# Eth-Crystal.net
KiCad netlist of a schematic drawn in Altium Designer
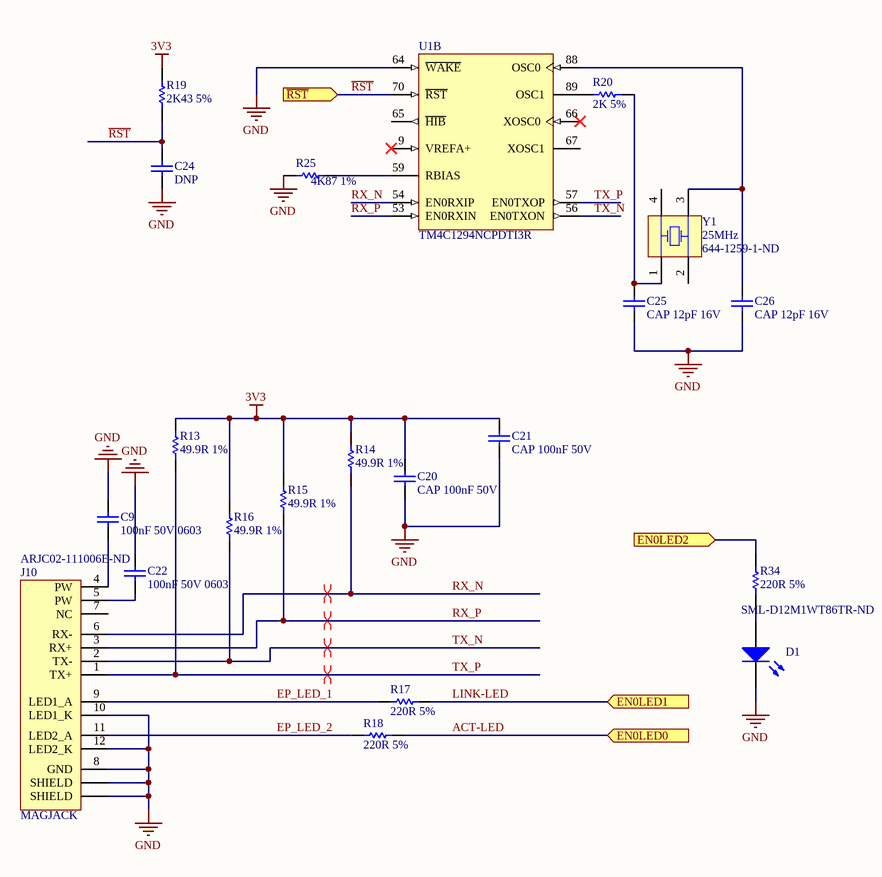
[diagram p0: Eth-Crystal.SchDoc]

(export (version "E")
  (design (tool "Eeschema 10.0.6"))
  (components
    (comp (ref "C9")
      (value "100nF 50V 0603")
      (footprint "CAPC0603(1608)100_M")
      (description "CAP 100nF 50V -20% to +80% 0603 (1608 Metric) Thickness 1mm SMD")
      (fields (field (name "TOLERANCE") "-20% to +80%"))
      (libsource (lib "Altium Content Vault") (part "CMP-1035-02594-1"))
    )
    (comp (ref "C20")
      (value "CAP 100nF 50V")
      (footprint "CAPC0603(1608)100_M")
      (description "CAP 100nF 50V Â±0.1pF 0603 (1608 Metric) Thickness 1mm SMD")
      (fields (field (name "TOLERANCE") "Â±0.1pF"))
      (libsource (lib "Altium Content Vault") (part "CMP-1035-00010-1"))
    )
    (comp (ref "C21")
      (value "CAP 100nF 50V")
      (footprint "CAPC0603(1608)100_M")
      (description "CAP 100nF 50V Â±0.1pF 0603 (1608 Metric) Thickness 1mm SMD")
      (fields (field (name "TOLERANCE") "Â±0.1pF"))
      (libsource (lib "Altium Content Vault") (part "CMP-1035-00010-1"))
    )
    (comp (ref "C22")
      (value "100nF 50V 0603")
      (footprint "CAPC0603(1608)100_M")
      (description "CAP 100nF 50V -20% to +80% 0603 (1608 Metric) Thickness 1mm SMD")
      (fields (field (name "TOLERANCE") "-20% to +80%"))
      (libsource (lib "Altium Content Vault") (part "CMP-1035-02594-1"))
    )
    (comp (ref "C24")
      (value "DNP")
      (footprint "0603")
      (description "100nF")
      (fields (field (name "PUBLISHER") "Altium Limited"))
      (libsource (lib "HSBNE-MAIN") (part "Cap_100pF"))
    )
    (comp (ref "C25")
      (value "CAP 12pF 16V")
      (footprint "CAPC0603(1608)100_L")
      (description "CAP 12pF 16V Â±0.25pF 0603 (1608 Metric) Thickness 1mm SMD")
      (fields (field (name "TOLERANCE") "Â±0.25pF"))
      (libsource (lib "Altium Content Vault") (part "CAP"))
    )
    (comp (ref "C26")
      (value "CAP 12pF 16V")
      (footprint "CAPC0603(1608)100_L")
      (description "CAP 12pF 16V Â±0.25pF 0603 (1608 Metric) Thickness 1mm SMD")
      (fields (field (name "TOLERANCE") "Â±0.25pF"))
      (libsource (lib "Altium Content Vault") (part "CAP"))
    )
    (comp (ref "D1")
      (value "LED")
      (footprint "LED-0603")
      (description "Typical RED, GREEN, YELLOW, AMBER GaAs LED")
      (fields
        (field (name "SUPPLIER PART NUMBER 2") "SML-D12M1WT86TR-ND")
        (field (name "PUBLISHER") "Altium Limited")
      )
      (libsource (lib "HSBNE-Vend") (part "LED"))
    )
    (comp (ref "J10")
      (value "MAGJACK")
      (footprint "magjack")
      (fields (field (name "SUPPLIER PART NUMBER 2") "ARJC02-111006E-ND"))
      (libsource (lib "HSBNE-MAIN") (part "MagJack"))
    )
    (comp (ref "R13")
      (value "49.9R 1%")
      (footprint "RESC0603(1608)_M")
      (description "49.9R 0.1W 1% 0603 (1608 Metric)  SMD")
      (fields (field (name "TOLERANCE") "5 %") (field (name "POWER") "0.1 W"))
      (libsource (lib "Altium Content Vault") (part "CMP-1012-00042-1"))
    )
    (comp (ref "R14")
      (value "49.9R 1%")
      (footprint "RESC0603(1608)_M")
      (description "49.9R 0.1W 1% 0603 (1608 Metric)  SMD")
      (fields (field (name "TOLERANCE") "5 %") (field (name "POWER") "0.1 W"))
      (libsource (lib "Altium Content Vault") (part "CMP-1012-00042-1"))
    )
    (comp (ref "R15")
      (value "49.9R 1%")
      (footprint "RESC0603(1608)_M")
      (description "49.9R 0.1W 1% 0603 (1608 Metric)  SMD")
      (fields (field (name "TOLERANCE") "5 %") (field (name "POWER") "0.1 W"))
      (libsource (lib "Altium Content Vault") (part "CMP-1012-00042-1"))
    )
    (comp (ref "R16")
      (value "49.9R 1%")
      (footprint "RESC0603(1608)_M")
      (description "49.9R 0.1W 1% 0603 (1608 Metric)  SMD")
      (fields (field (name "TOLERANCE") "5 %") (field (name "POWER") "0.1 W"))
      (libsource (lib "Altium Content Vault") (part "CMP-1012-00042-1"))
    )
    (comp (ref "R17")
      (value "220R 5%")
      (footprint "RESC0603(1608)_M")
      (description "220R 0.1W 5% 0603 (1608 Metric)  SMD")
      (fields (field (name "POWER") "0.1 W") (field (name "TOLERANCE") "5 %"))
      (libsource (lib "Altium Content Vault") (part "CMP-1012-00058-1"))
    )
    (comp (ref "R18")
      (value "220R 5%")
      (footprint "RESC0603(1608)_M")
      (description "220R 0.1W 5% 0603 (1608 Metric)  SMD")
      (fields (field (name "POWER") "0.1 W") (field (name "TOLERANCE") "5 %"))
      (libsource (lib "Altium Content Vault") (part "CMP-1012-00058-1"))
    )
    (comp (ref "R19")
      (value "2K43 5%")
      (footprint "RESC0603(1608)_M")
      (description "2K43 0.1W 5% 0603 (1608 Metric)  SMD")
      (fields (field (name "TOLERANCE") "5 %") (field (name "POWER") "0.1 W"))
      (libsource (lib "Altium Content Vault") (part "CMP-1012-00083-1"))
    )
    (comp (ref "R20")
      (value "2K 5%")
      (footprint "RESC0603(1608)_N")
      (description "2K 0.1W 5% 0603 (1608 Metric)  SMD")
      (fields (field (name "TOLERANCE") "5 %") (field (name "POWER") "0.1 W"))
      (libsource (lib "Altium Content Vault") (part "RES"))
    )
    (comp (ref "R25")
      (value "4K87 1%")
      (footprint "RESC0603(1608)_M")
      (description "4K87 0.1W 1% 0603 (1608 Metric)  SMD")
      (fields (field (name "TOLERANCE") "5 %") (field (name "POWER") "0.1 W"))
      (libsource (lib "Altium Content Vault") (part "CMP-1012-00090-1"))
    )
    (comp (ref "R34")
      (value "220R 5%")
      (footprint "RESC0603(1608)_M")
      (description "220R 0.1W 5% 0603 (1608 Metric)  SMD")
      (fields (field (name "POWER") "0.1 W") (field (name "TOLERANCE") "5 %"))
      (libsource (lib "Altium Content Vault") (part "CMP-1012-00058-1"))
    )
    (comp (ref "U1")
      (value "TM4C1294NCPDTI3R")
      (footprint "TI-PDT128_M")
      (fields (field (name "MANUFACTURER") "Texas Instruments"))
      (libsource (lib "Altium Inc") (part "TI-TM4C1294NCPDT-128"))
    )
    (comp (ref "Y1")
      (value "25MHz")
      (footprint "Crystal 3.2x2.5")
      (description "Surface Mount Quartz Crystal")
      (fields
        (field (name "SUPPLIER PART NUMBER 1") "644-1259-1-ND")
        (field (name "PUBLISHER") "Altium Limited")
      )
      (libsource (lib "HSBNE-Vend") (part "Crystal_25MHz"))
    )
  )
  (nets
    (net (code "1") (name "/ACT-LED") (class "Default")
      (node (ref "R18") (pin "2") (pinfunction "2_2") (pintype "passive"))
    )
    (net (code "2") (name "/EN0LED2") (class "Default")
      (node (ref "R34") (pin "2") (pinfunction "2_2") (pintype "passive"))
    )
    (net (code "3") (name "/EP_LED_1") (class "Default")
      (node (ref "J10") (pin "9") (pinfunction "LED1_A_9") (pintype "passive"))
      (node (ref "R17") (pin "1") (pinfunction "1_1") (pintype "passive"))
    )
    (net (code "4") (name "/EP_LED_2") (class "Default")
      (node (ref "J10") (pin "11") (pinfunction "LED2_A_11") (pintype "passive"))
      (node (ref "R18") (pin "1") (pinfunction "1_1") (pintype "passive"))
    )
    (net (code "5") (name "/LINK-LED") (class "Default")
      (node (ref "R17") (pin "2") (pinfunction "2_2") (pintype "passive"))
    )
    (net (code "6") (name "/RX_N") (class "Default")
      (node (ref "J10") (pin "6") (pinfunction "RX-_6") (pintype "passive"))
      (node (ref "R14") (pin "1") (pinfunction "1_1") (pintype "passive"))
      (node (ref "U1") (pin "54") (pinfunction "EN0RXIP_54") (pintype "input"))
    )
    (net (code "7") (name "/RX_P") (class "Default")
      (node (ref "J10") (pin "3") (pinfunction "RX+_3") (pintype "passive"))
      (node (ref "R15") (pin "1") (pinfunction "1_1") (pintype "passive"))
      (node (ref "U1") (pin "53") (pinfunction "EN0RXIN_53") (pintype "input"))
    )
    (net (code "8") (name "/TX_N") (class "Default")
      (node (ref "J10") (pin "2") (pinfunction "TX-_2") (pintype "passive"))
      (node (ref "R16") (pin "1") (pinfunction "1_1") (pintype "passive"))
      (node (ref "U1") (pin "56") (pinfunction "EN0TXON_56") (pintype "output"))
    )
    (net (code "9") (name "/TX_P") (class "Default")
      (node (ref "J10") (pin "1") (pinfunction "TX+_1") (pintype "passive"))
      (node (ref "R13") (pin "1") (pinfunction "1_1") (pintype "passive"))
      (node (ref "U1") (pin "57") (pinfunction "EN0TXOP_57") (pintype "output"))
    )
    (net (code "10") (name "/~{RST}") (class "Default")
      (node (ref "C24") (pin "2") (pinfunction "2_2") (pintype "passive"))
      (node (ref "R19") (pin "1") (pinfunction "1_1") (pintype "passive"))
      (node (ref "U1") (pin "70") (pinfunction "~{RST}_70") (pintype "input"))
    )
    (net (code "11") (name "3V3") (class "Default")
      (node (ref "C20") (pin "2") (pinfunction "2_2") (pintype "passive"))
      (node (ref "C21") (pin "2") (pinfunction "2_2") (pintype "passive"))
      (node (ref "R13") (pin "2") (pinfunction "2_2") (pintype "passive"))
      (node (ref "R14") (pin "2") (pinfunction "2_2") (pintype "passive"))
      (node (ref "R15") (pin "2") (pinfunction "2_2") (pintype "passive"))
      (node (ref "R16") (pin "2") (pinfunction "2_2") (pintype "passive"))
      (node (ref "R19") (pin "2") (pinfunction "2_2") (pintype "passive"))
    )
    (net (code "12") (name "GND") (class "Default")
      (node (ref "C20") (pin "1") (pinfunction "1_1") (pintype "passive"))
      (node (ref "C21") (pin "1") (pinfunction "1_1") (pintype "passive"))
      (node (ref "C22") (pin "2") (pinfunction "2_2") (pintype "passive"))
      (node (ref "C24") (pin "1") (pinfunction "1_1") (pintype "passive"))
      (node (ref "C25") (pin "1") (pinfunction "1_1") (pintype "passive"))
      (node (ref "C26") (pin "1") (pinfunction "1_1") (pintype "passive"))
      (node (ref "C9") (pin "2") (pinfunction "2_2") (pintype "passive"))
      (node (ref "D1") (pin "2") (pinfunction "K_2") (pintype "passive"))
      (node (ref "J10") (pin "10") (pinfunction "LED1_K_10") (pintype "passive"))
      (node (ref "J10") (pin "12") (pinfunction "LED2_K_12") (pintype "passive"))
      (node (ref "J10") (pin "8") (pinfunction "GND_8") (pintype "passive"))
      (node (ref "J10") (pin "GND1") (pinfunction "SHIELD_GND1") (pintype "passive"))
      (node (ref "J10") (pin "GND2") (pinfunction "SHIELD_GND2") (pintype "passive"))
      (node (ref "R25") (pin "1") (pinfunction "1_1") (pintype "passive"))
      (node (ref "U1") (pin "64") (pinfunction "~{WAKE}_64") (pintype "input"))
    )
    (net (code "13") (name "Net-(C9-Pad1)") (class "Default")
      (node (ref "C9") (pin "1") (pinfunction "1_1") (pintype "passive"))
      (node (ref "J10") (pin "4") (pinfunction "PW_4") (pintype "passive"))
    )
    (net (code "14") (name "Net-(C22-Pad1)") (class "Default")
      (node (ref "C22") (pin "1") (pinfunction "1_1") (pintype "passive"))
      (node (ref "J10") (pin "5") (pinfunction "PW_5") (pintype "passive"))
    )
    (net (code "15") (name "Net-(C25-Pad2)") (class "Default")
      (node (ref "C25") (pin "2") (pinfunction "2_2") (pintype "passive"))
      (node (ref "R20") (pin "2") (pinfunction "2_2") (pintype "passive"))
      (node (ref "Y1") (pin "1") (pinfunction "OSC1_1") (pintype "passive"))
    )
    (net (code "16") (name "Net-(D1-A)") (class "Default")
      (node (ref "D1") (pin "1") (pinfunction "A_1") (pintype "passive"))
      (node (ref "R34") (pin "1") (pinfunction "1_1") (pintype "passive"))
    )
    (net (code "17") (name "Net-(U1B-OSC0)") (class "Default")
      (node (ref "C26") (pin "2") (pinfunction "2_2") (pintype "passive"))
      (node (ref "U1") (pin "88") (pinfunction "OSC0_88") (pintype "input"))
      (node (ref "Y1") (pin "3") (pinfunction "OSC2_3") (pintype "passive"))
    )
    (net (code "18") (name "Net-(U1B-OSC1)") (class "Default")
      (node (ref "R20") (pin "1") (pinfunction "1_1") (pintype "passive"))
      (node (ref "U1") (pin "89") (pinfunction "OSC1_89") (pintype "passive"))
    )
    (net (code "19") (name "Net-(U1B-RBIAS)") (class "Default")
      (node (ref "R25") (pin "2") (pinfunction "2_2") (pintype "passive"))
      (node (ref "U1") (pin "59") (pinfunction "RBIAS_59") (pintype "passive"))
    )
    (net (code "20") (name "unconnected-(J10-NC-Pad7)") (class "Default")
      (node (ref "J10") (pin "7") (pinfunction "NC_7") (pintype "passive"))
    )
    (net (code "21") (name "unconnected-(U1B-VREFA+-Pad9)") (class "Default")
      (node (ref "U1") (pin "9") (pinfunction "VREFA+_9") (pintype "input+no_connect"))
    )
    (net (code "22") (name "unconnected-(U1B-XOSC0-Pad66)") (class "Default")
      (node (ref "U1") (pin "66") (pinfunction "XOSC0_66") (pintype "input+no_connect"))
    )
    (net (code "23") (name "unconnected-(U1B-XOSC1-Pad67)") (class "Default")
      (node (ref "U1") (pin "67") (pinfunction "XOSC1_67") (pintype "passive"))
    )
    (net (code "24") (name "unconnected-(U1B-~{HIB}-Pad65)") (class "Default")
      (node (ref "U1") (pin "65") (pinfunction "~{HIB}_65") (pintype "output"))
    )
    (net (code "25") (name "unconnected-(Y1-OSC1-Pad4)") (class "Default")
      (node (ref "Y1") (pin "4") (pinfunction "OSC1_4") (pintype "passive"))
    )
    (net (code "26") (name "unconnected-(Y1-OSC2-Pad2)") (class "Default")
      (node (ref "Y1") (pin "2") (pinfunction "OSC2_2") (pintype "passive"))
    )
  )
)
